# I2C_schematic.net
KiCad netlist of a schematic drawn in Altium Designer
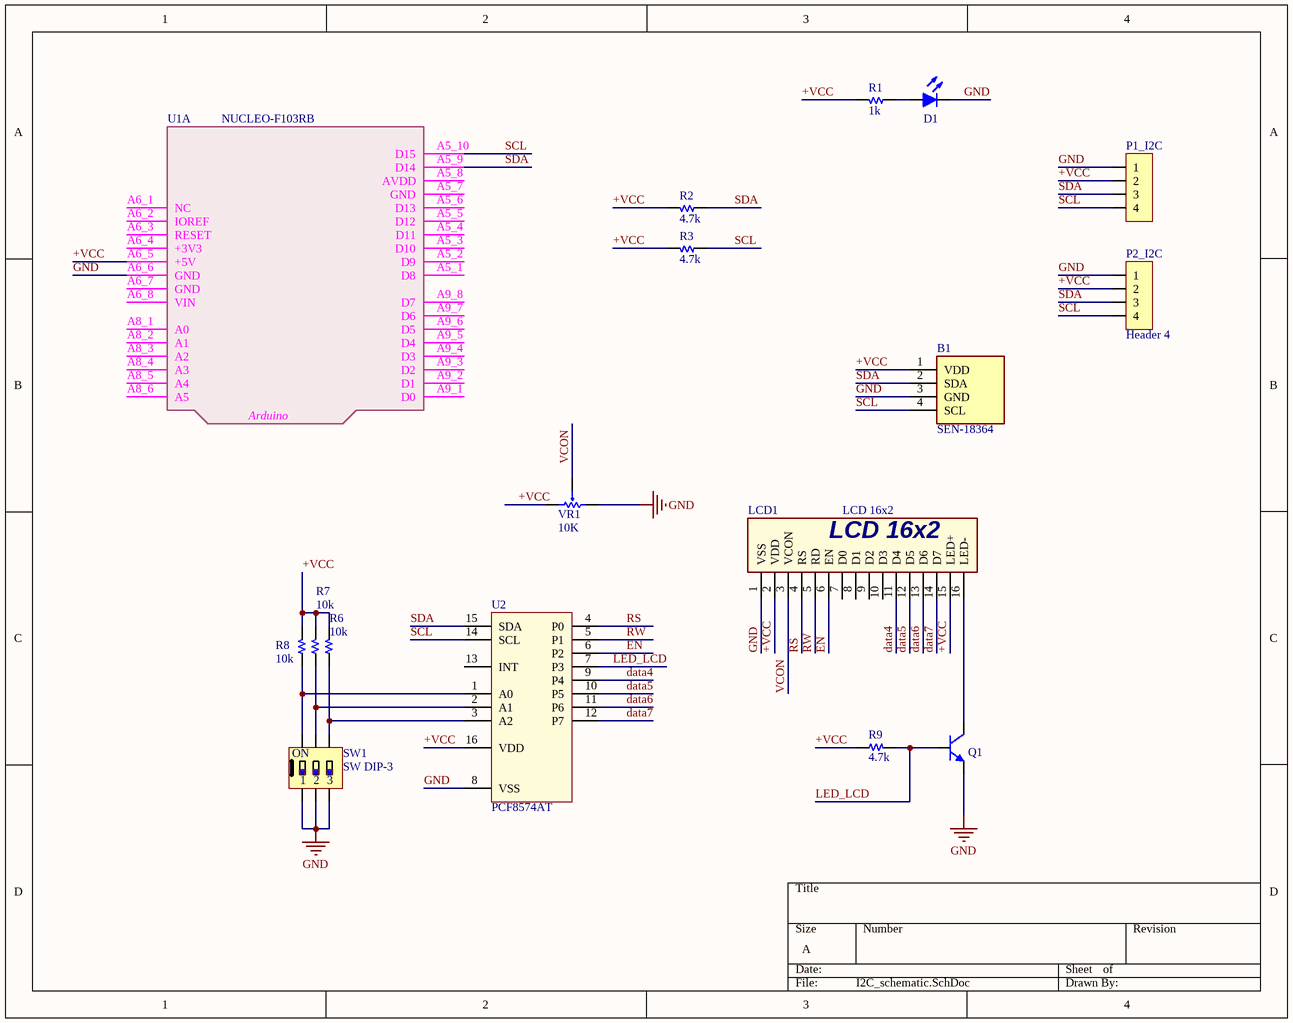
[diagram p0: I2C_schematic.SchDoc]

(export (version "E")
  (design (tool "Eeschema 10.0.6"))
  (components
    (comp (ref "B1")
      (value "SEN-18364")
      (footprint "SEN18364:SEN18364")
      (description "Multiple Function Sensor Modules Humidity and Temperature Sensor - DHT20")
      (fields (field (name "MOUSER PART NUMBER") "474-SEN-18364"))
      (libsource (lib "chipfc_altium_libs") (part "SEN-18364"))
    )
    (comp (ref "D1")
      (value "Led")
      (footprint "LED 3MM - red")
      (description "Typical LED")
      (libsource (lib "chipfc_altium_libs") (part "Led"))
    )
    (comp (ref "LCD1")
      (value "LCD 16x2")
      (footprint "LCD 1602B")
      (description "Character LCD 16x2")
      (libsource (lib "chipfc_altium_libs") (part "LCD 16x2"))
    )
    (comp (ref "P1_I2C")
      (value "~")
      (footprint "HDR/Header/4/2mm/BOX")
      (description "Header, 4-Pin")
      (libsource (lib "chipfc_altium_libs") (part "Header 4"))
    )
    (comp (ref "P2_I2C")
      (value "Header 4")
      (footprint "HDR/Header/4/2mm/BOX")
      (description "Header, 4-Pin")
      (libsource (lib "chipfc_altium_libs") (part "Header 4"))
    )
    (comp (ref "Q1")
      (value "Transistor NPN")
      (footprint "TO-92/W100")
      (description "NPN Bipolar Transistor")
      (libsource (lib "chipfc_altium_libs") (part "Transistor NPN"))
    )
    (comp (ref "R1")
      (value "1k")
      (footprint "R 1/4W/300")
      (description "Resistor")
      (libsource (lib "chipfc_altium_libs") (part "Resistor"))
    )
    (comp (ref "R2")
      (value "4.7k")
      (footprint "R 1/4W/300")
      (description "Resistor")
      (libsource (lib "chipfc_altium_libs") (part "Resistor"))
    )
    (comp (ref "R3")
      (value "4.7k")
      (footprint "R 1/4W/300")
      (description "Resistor")
      (libsource (lib "chipfc_altium_libs") (part "Resistor"))
    )
    (comp (ref "R6")
      (value "10k")
      (footprint "R 1/4W/300")
      (description "Resistor")
      (libsource (lib "chipfc_altium_libs") (part "Resistor"))
    )
    (comp (ref "R7")
      (value "10k")
      (footprint "R 1/4W/300")
      (description "Resistor")
      (libsource (lib "chipfc_altium_libs") (part "Resistor"))
    )
    (comp (ref "R8")
      (value "10k")
      (footprint "R 1/4W/300")
      (description "Resistor")
      (libsource (lib "chipfc_altium_libs") (part "Resistor"))
    )
    (comp (ref "R9")
      (value "4.7k")
      (footprint "R 1/4W/300")
      (description "Resistor")
      (libsource (lib "chipfc_altium_libs") (part "Resistor"))
    )
    (comp (ref "SW1")
      (value "SW DIP-3")
      (footprint "SW/DIP3")
      (libsource (lib "chipfc_altium_libs") (part "SW DIP-3"))
    )
    (comp (ref "U1")
      (value "NUCLEO-F103RB")
      (footprint "NUCLEO")
      (fields (field (name "MANUFACTURER") "STMicroelectronics"))
      (libsource (lib "nucleo") (part "NUCLEO-F103RB"))
    )
    (comp (ref "U2")
      (value "PCF8574AT")
      (footprint "DIP16")
      (description "Remote 8-bit I/O expander for I2C-bus with interrupt")
      (fields (field (name "PART NO") "PCF8574AT/3"))
      (libsource (lib "chipfc_altium_libs") (part "PCF8574AT"))
    )
    (comp (ref "VR1")
      (value "10K")
      (footprint "R VAR A 3D")
      (description "Resistor Variable")
      (libsource (lib "chipfc_altium_libs") (part "Resistor Variable"))
    )
  )
  (nets
    (net (code "1") (name "/+VCC") (class "Default")
      (node (ref "B1") (pin "1") (pinfunction "VDD_1") (pintype "passive"))
      (node (ref "LCD1") (pin "15") (pinfunction "LED+_15") (pintype "passive"))
      (node (ref "LCD1") (pin "2") (pinfunction "VDD_2") (pintype "passive"))
      (node (ref "P1_I2C") (pin "2") (pinfunction "2_2") (pintype "passive"))
      (node (ref "P2_I2C") (pin "2") (pinfunction "2_2") (pintype "passive"))
      (node (ref "R1") (pin "2") (pinfunction "2_2") (pintype "passive"))
      (node (ref "R2") (pin "2") (pinfunction "2_2") (pintype "passive"))
      (node (ref "R3") (pin "2") (pinfunction "2_2") (pintype "passive"))
      (node (ref "R6") (pin "2") (pinfunction "2_2") (pintype "passive"))
      (node (ref "R7") (pin "2") (pinfunction "2_2") (pintype "passive"))
      (node (ref "R8") (pin "2") (pinfunction "2_2") (pintype "passive"))
      (node (ref "R9") (pin "1") (pinfunction "1_1") (pintype "passive"))
      (node (ref "U1") (pin "A6_5") (pinfunction "+5V_A6_5") (pintype "passive"))
      (node (ref "U2") (pin "16") (pinfunction "VDD_16") (pintype "passive"))
      (node (ref "VR1") (pin "1") (pinfunction "1_1") (pintype "passive"))
    )
    (net (code "2") (name "/EN") (class "Default")
      (node (ref "LCD1") (pin "6") (pinfunction "EN_6") (pintype "passive"))
      (node (ref "U2") (pin "6") (pinfunction "P2_6") (pintype "passive"))
    )
    (net (code "3") (name "/LED_LCD") (class "Default")
      (node (ref "Q1") (pin "1") (pinfunction "B_1") (pintype "passive"))
      (node (ref "R9") (pin "2") (pinfunction "2_2") (pintype "passive"))
      (node (ref "U2") (pin "7") (pinfunction "P3_7") (pintype "passive"))
    )
    (net (code "4") (name "/RS") (class "Default")
      (node (ref "LCD1") (pin "4") (pinfunction "RS_4") (pintype "passive"))
      (node (ref "U2") (pin "4") (pinfunction "P0_4") (pintype "passive"))
    )
    (net (code "5") (name "/RW") (class "Default")
      (node (ref "LCD1") (pin "5") (pinfunction "RD_5") (pintype "passive"))
      (node (ref "U2") (pin "5") (pinfunction "P1_5") (pintype "passive"))
    )
    (net (code "6") (name "/SCL") (class "Default")
      (node (ref "B1") (pin "4") (pinfunction "SCL_4") (pintype "passive"))
      (node (ref "P1_I2C") (pin "4") (pinfunction "4_4") (pintype "passive"))
      (node (ref "P2_I2C") (pin "4") (pinfunction "4_4") (pintype "passive"))
      (node (ref "R3") (pin "1") (pinfunction "1_1") (pintype "passive"))
      (node (ref "U1") (pin "A5_10") (pinfunction "D15_A5_10") (pintype "passive"))
      (node (ref "U2") (pin "14") (pinfunction "SCL_14") (pintype "passive"))
    )
    (net (code "7") (name "/SDA") (class "Default")
      (node (ref "B1") (pin "2") (pinfunction "SDA_2") (pintype "passive"))
      (node (ref "P1_I2C") (pin "3") (pinfunction "3_3") (pintype "passive"))
      (node (ref "P2_I2C") (pin "3") (pinfunction "3_3") (pintype "passive"))
      (node (ref "R2") (pin "1") (pinfunction "1_1") (pintype "passive"))
      (node (ref "U1") (pin "A5_9") (pinfunction "D14_A5_9") (pintype "passive"))
      (node (ref "U2") (pin "15") (pinfunction "SDA_15") (pintype "passive"))
    )
    (net (code "8") (name "/VCON") (class "Default")
      (node (ref "LCD1") (pin "3") (pinfunction "VCON_3") (pintype "passive"))
      (node (ref "VR1") (pin "2") (pinfunction "2_2") (pintype "passive"))
    )
    (net (code "9") (name "/data4") (class "Default")
      (node (ref "LCD1") (pin "11") (pinfunction "D4_11") (pintype "passive"))
      (node (ref "U2") (pin "9") (pinfunction "P4_9") (pintype "passive"))
    )
    (net (code "10") (name "/data5") (class "Default")
      (node (ref "LCD1") (pin "12") (pinfunction "D5_12") (pintype "passive"))
      (node (ref "U2") (pin "10") (pinfunction "P5_10") (pintype "passive"))
    )
    (net (code "11") (name "/data6") (class "Default")
      (node (ref "LCD1") (pin "13") (pinfunction "D6_13") (pintype "passive"))
      (node (ref "U2") (pin "11") (pinfunction "P6_11") (pintype "passive"))
    )
    (net (code "12") (name "/data7") (class "Default")
      (node (ref "LCD1") (pin "14") (pinfunction "D7_14") (pintype "passive"))
      (node (ref "U2") (pin "12") (pinfunction "P7_12") (pintype "passive"))
    )
    (net (code "13") (name "GND") (class "Default")
      (node (ref "B1") (pin "3") (pinfunction "GND_3") (pintype "passive"))
      (node (ref "D1") (pin "2") (pinfunction "K_2") (pintype "passive"))
      (node (ref "LCD1") (pin "1") (pinfunction "VSS_1") (pintype "passive"))
      (node (ref "P1_I2C") (pin "1") (pinfunction "1_1") (pintype "passive"))
      (node (ref "P2_I2C") (pin "1") (pinfunction "1_1") (pintype "passive"))
      (node (ref "Q1") (pin "2") (pinfunction "E_2") (pintype "passive"))
      (node (ref "SW1") (pin "1") (pinfunction "1_1") (pintype "passive"))
      (node (ref "SW1") (pin "2") (pinfunction "2_2") (pintype "passive"))
      (node (ref "SW1") (pin "3") (pinfunction "3_3") (pintype "passive"))
      (node (ref "U1") (pin "A6_6") (pinfunction "GND_A6_6") (pintype "passive"))
      (node (ref "U2") (pin "8") (pinfunction "VSS_8") (pintype "passive"))
      (node (ref "VR1") (pin "3") (pinfunction "3_3") (pintype "passive"))
    )
    (net (code "14") (name "Net-(D1-A)") (class "Default")
      (node (ref "D1") (pin "1") (pinfunction "A_1") (pintype "passive"))
      (node (ref "R1") (pin "1") (pinfunction "1_1") (pintype "passive"))
    )
    (net (code "15") (name "Net-(LCD1-LED-)") (class "Default")
      (node (ref "LCD1") (pin "16") (pinfunction "LED-_16") (pintype "passive"))
      (node (ref "Q1") (pin "3") (pinfunction "C_3") (pintype "passive"))
    )
    (net (code "16") (name "Net-(U2-A0)") (class "Default")
      (node (ref "R8") (pin "1") (pinfunction "1_1") (pintype "passive"))
      (node (ref "SW1") (pin "6") (pinfunction "6_6") (pintype "passive"))
      (node (ref "U2") (pin "1") (pinfunction "A0_1") (pintype "passive"))
    )
    (net (code "17") (name "Net-(U2-A1)") (class "Default")
      (node (ref "R7") (pin "1") (pinfunction "1_1") (pintype "passive"))
      (node (ref "SW1") (pin "5") (pinfunction "5_5") (pintype "passive"))
      (node (ref "U2") (pin "2") (pinfunction "A1_2") (pintype "passive"))
    )
    (net (code "18") (name "Net-(U2-A2)") (class "Default")
      (node (ref "R6") (pin "1") (pinfunction "1_1") (pintype "passive"))
      (node (ref "SW1") (pin "4") (pinfunction "4_4") (pintype "passive"))
      (node (ref "U2") (pin "3") (pinfunction "A2_3") (pintype "passive"))
    )
    (net (code "19") (name "unconnected-(LCD1-D0-Pad7)") (class "Default")
      (node (ref "LCD1") (pin "7") (pinfunction "D0_7") (pintype "passive"))
    )
    (net (code "20") (name "unconnected-(LCD1-D1-Pad8)") (class "Default")
      (node (ref "LCD1") (pin "8") (pinfunction "D1_8") (pintype "passive"))
    )
    (net (code "21") (name "unconnected-(LCD1-D2-Pad9)") (class "Default")
      (node (ref "LCD1") (pin "9") (pinfunction "D2_9") (pintype "passive"))
    )
    (net (code "22") (name "unconnected-(LCD1-D3-Pad10)") (class "Default")
      (node (ref "LCD1") (pin "10") (pinfunction "D3_10") (pintype "passive"))
    )
    (net (code "23") (name "unconnected-(U1A-+3V3-PadA6_4)") (class "Default")
      (node (ref "U1") (pin "A6_4") (pinfunction "+3V3_A6_4") (pintype "passive"))
    )
    (net (code "24") (name "unconnected-(U1A-A0-PadA8_1)") (class "Default")
      (node (ref "U1") (pin "A8_1") (pinfunction "A0_A8_1") (pintype "passive"))
    )
    (net (code "25") (name "unconnected-(U1A-A1-PadA8_2)") (class "Default")
      (node (ref "U1") (pin "A8_2") (pinfunction "A1_A8_2") (pintype "passive"))
    )
    (net (code "26") (name "unconnected-(U1A-A2-PadA8_3)") (class "Default")
      (node (ref "U1") (pin "A8_3") (pinfunction "A2_A8_3") (pintype "passive"))
    )
    (net (code "27") (name "unconnected-(U1A-A3-PadA8_4)") (class "Default")
      (node (ref "U1") (pin "A8_4") (pinfunction "A3_A8_4") (pintype "passive"))
    )
    (net (code "28") (name "unconnected-(U1A-A4-PadA8_5)") (class "Default")
      (node (ref "U1") (pin "A8_5") (pinfunction "A4_A8_5") (pintype "passive"))
    )
    (net (code "29") (name "unconnected-(U1A-A5-PadA8_6)") (class "Default")
      (node (ref "U1") (pin "A8_6") (pinfunction "A5_A8_6") (pintype "passive"))
    )
    (net (code "30") (name "unconnected-(U1A-AVDD-PadA5_8)") (class "Default")
      (node (ref "U1") (pin "A5_8") (pinfunction "AVDD_A5_8") (pintype "passive"))
    )
    (net (code "31") (name "unconnected-(U1A-D0-PadA9_1)") (class "Default")
      (node (ref "U1") (pin "A9_1") (pinfunction "D0_A9_1") (pintype "passive"))
    )
    (net (code "32") (name "unconnected-(U1A-D1-PadA9_2)") (class "Default")
      (node (ref "U1") (pin "A9_2") (pinfunction "D1_A9_2") (pintype "passive"))
    )
    (net (code "33") (name "unconnected-(U1A-D2-PadA9_3)") (class "Default")
      (node (ref "U1") (pin "A9_3") (pinfunction "D2_A9_3") (pintype "passive"))
    )
    (net (code "34") (name "unconnected-(U1A-D3-PadA9_4)") (class "Default")
      (node (ref "U1") (pin "A9_4") (pinfunction "D3_A9_4") (pintype "passive"))
    )
    (net (code "35") (name "unconnected-(U1A-D4-PadA9_5)") (class "Default")
      (node (ref "U1") (pin "A9_5") (pinfunction "D4_A9_5") (pintype "passive"))
    )
    (net (code "36") (name "unconnected-(U1A-D5-PadA9_6)") (class "Default")
      (node (ref "U1") (pin "A9_6") (pinfunction "D5_A9_6") (pintype "passive"))
    )
    (net (code "37") (name "unconnected-(U1A-D6-PadA9_7)") (class "Default")
      (node (ref "U1") (pin "A9_7") (pinfunction "D6_A9_7") (pintype "passive"))
    )
    (net (code "38") (name "unconnected-(U1A-D7-PadA9_8)") (class "Default")
      (node (ref "U1") (pin "A9_8") (pinfunction "D7_A9_8") (pintype "passive"))
    )
    (net (code "39") (name "unconnected-(U1A-D8-PadA5_1)") (class "Default")
      (node (ref "U1") (pin "A5_1") (pinfunction "D8_A5_1") (pintype "passive"))
    )
    (net (code "40") (name "unconnected-(U1A-D9-PadA5_2)") (class "Default")
      (node (ref "U1") (pin "A5_2") (pinfunction "D9_A5_2") (pintype "passive"))
    )
    (net (code "41") (name "unconnected-(U1A-D10-PadA5_3)") (class "Default")
      (node (ref "U1") (pin "A5_3") (pinfunction "D10_A5_3") (pintype "passive"))
    )
    (net (code "42") (name "unconnected-(U1A-D11-PadA5_4)") (class "Default")
      (node (ref "U1") (pin "A5_4") (pinfunction "D11_A5_4") (pintype "passive"))
    )
    (net (code "43") (name "unconnected-(U1A-D12-PadA5_5)") (class "Default")
      (node (ref "U1") (pin "A5_5") (pinfunction "D12_A5_5") (pintype "passive"))
    )
    (net (code "44") (name "unconnected-(U1A-D13-PadA5_6)") (class "Default")
      (node (ref "U1") (pin "A5_6") (pinfunction "D13_A5_6") (pintype "passive"))
    )
    (net (code "45") (name "unconnected-(U1A-GND-PadA5_7)") (class "Default")
      (node (ref "U1") (pin "A5_7") (pinfunction "GND_A5_7") (pintype "passive"))
    )
    (net (code "46") (name "unconnected-(U1A-GND-PadA6_7)") (class "Default")
      (node (ref "U1") (pin "A6_7") (pinfunction "GND_A6_7") (pintype "passive"))
    )
    (net (code "47") (name "unconnected-(U1A-IOREF-PadA6_2)") (class "Default")
      (node (ref "U1") (pin "A6_2") (pinfunction "IOREF_A6_2") (pintype "passive"))
    )
    (net (code "48") (name "unconnected-(U1A-NC-PadA6_1)") (class "Default")
      (node (ref "U1") (pin "A6_1") (pinfunction "NC_A6_1") (pintype "passive"))
    )
    (net (code "49") (name "unconnected-(U1A-RESET-PadA6_3)") (class "Default")
      (node (ref "U1") (pin "A6_3") (pinfunction "RESET_A6_3") (pintype "passive"))
    )
    (net (code "50") (name "unconnected-(U1A-VIN-PadA6_8)") (class "Default")
      (node (ref "U1") (pin "A6_8") (pinfunction "VIN_A6_8") (pintype "passive"))
    )
    (net (code "51") (name "unconnected-(U2-INT-Pad13)") (class "Default")
      (node (ref "U2") (pin "13") (pinfunction "INT_13") (pintype "passive"))
    )
  )
)
